# Voltage_Reference.net
KiCad netlist of a schematic drawn in Altium Designer
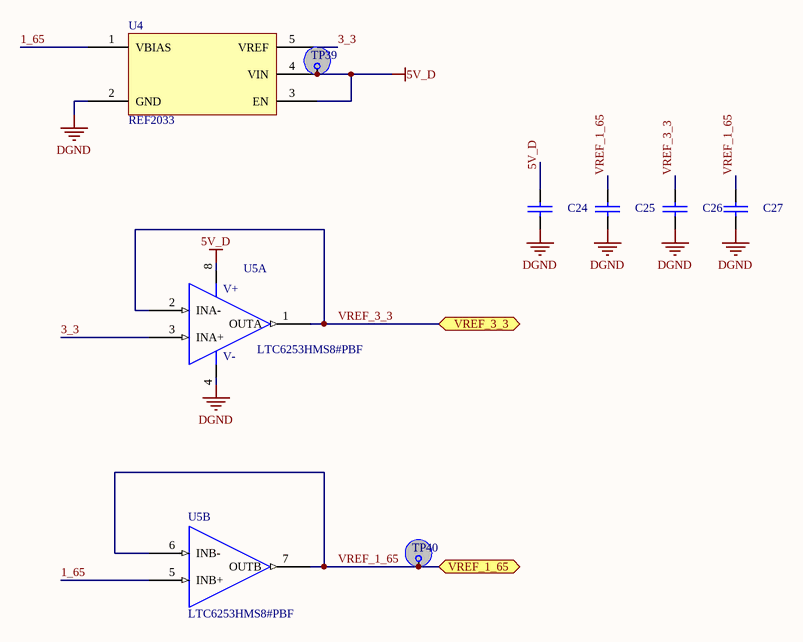
[diagram p0: Voltage Reference.SchDoc]

(export (version "E")
  (design (tool "Eeschema 10.0.6"))
  (components
    (comp (ref "C24")
      (value "CAP 0603 100nF 100V")
      (footprint "CAPC1608N")
      (description "CAP 0603 TBD")
      (fields (field (name "PART#") "TBD"))
      (libsource (lib "SMD_R&C_V1.0") (part "CAP 0603 TBD"))
    )
    (comp (ref "C25")
      (value "CAP 0603 100nF 100V")
      (footprint "CAPC1608N")
      (description "CAP 0603 TBD")
      (fields (field (name "PART#") "TBD"))
      (libsource (lib "SMD_R&C_V1.0") (part "CAP 0603 TBD"))
    )
    (comp (ref "C26")
      (value "CAP 0603 100nF 100V")
      (footprint "CAPC1608N")
      (description "CAP 0603 TBD")
      (fields (field (name "PART#") "TBD"))
      (libsource (lib "SMD_R&C_V1.0") (part "CAP 0603 TBD"))
    )
    (comp (ref "C27")
      (value "CAP 0603 100nF 100V")
      (footprint "CAPC1608N")
      (description "CAP 0603 TBD")
      (fields (field (name "PART#") "TBD"))
      (libsource (lib "SMD_R&C_V1.0") (part "CAP 0603 TBD"))
    )
    (comp (ref "TP39")
      (value "*")
      (footprint "Keystone 5000")
      (libsource (lib "Aarons_Library") (part "TEST_POINT_HOOK"))
    )
    (comp (ref "TP40")
      (value "*")
      (footprint "Keystone 5000")
      (libsource (lib "Aarons_Library") (part "TEST_POINT_HOOK"))
    )
    (comp (ref "U4")
      (value "REF2033")
      (footprint "SOT-23 5 PIN")
      (libsource (lib "Aarons_Library") (part "REF2033"))
    )
    (comp (ref "U5")
      (value "LTC6253HMS8#PBF")
      (footprint "SOIC-8")
      (description "720MHz, 3.5mA Power\r\nEfficient Rail-to-Rail\r\nI/O Op Amps")
      (fields
        (field (name "MANUFACTURER") "Texas Instruments")
        (field (name "GENERIC_PART_NUMBER") "OPA2140")
      )
      (libsource (lib "Analog_Op-amp") (part "LTC6253HMS8#PBF"))
    )
  )
  (nets
    (net (code "1") (name "/1_65") (class "Default")
      (node (ref "U4") (pin "1") (pinfunction "VBIAS_1") (pintype "passive"))
      (node (ref "U5") (pin "5") (pinfunction "INB+_5") (pintype "input"))
    )
    (net (code "2") (name "/3_3") (class "Default")
      (node (ref "U4") (pin "5") (pinfunction "VREF_5") (pintype "passive"))
      (node (ref "U5") (pin "3") (pinfunction "INA+_3") (pintype "input"))
    )
    (net (code "3") (name "/VREF_1_65") (class "Default")
      (node (ref "C25") (pin "2") (pintype "passive"))
      (node (ref "C27") (pin "2") (pintype "passive"))
      (node (ref "TP40") (pin "1") (pinfunction "1_1") (pintype "passive"))
      (node (ref "U5") (pin "6") (pinfunction "INB-_6") (pintype "input"))
      (node (ref "U5") (pin "7") (pinfunction "OUTB_7") (pintype "output"))
    )
    (net (code "4") (name "/VREF_3_3") (class "Default")
      (node (ref "C26") (pin "2") (pintype "passive"))
      (node (ref "U5") (pin "1") (pinfunction "OUTA_1") (pintype "output"))
      (node (ref "U5") (pin "2") (pinfunction "INA-_2") (pintype "input"))
    )
    (net (code "5") (name "5V_D") (class "Default")
      (node (ref "C24") (pin "2") (pintype "passive"))
      (node (ref "TP39") (pin "1") (pinfunction "1_1") (pintype "passive"))
      (node (ref "U4") (pin "3") (pinfunction "EN_3") (pintype "passive"))
      (node (ref "U4") (pin "4") (pinfunction "VIN_4") (pintype "passive"))
      (node (ref "U5") (pin "8") (pinfunction "V+_8") (pintype "power_in"))
    )
    (net (code "6") (name "DGND") (class "Default")
      (node (ref "C24") (pin "1") (pintype "passive"))
      (node (ref "C25") (pin "1") (pintype "passive"))
      (node (ref "C26") (pin "1") (pintype "passive"))
      (node (ref "C27") (pin "1") (pintype "passive"))
      (node (ref "U4") (pin "2") (pinfunction "GND_2") (pintype "passive"))
      (node (ref "U5") (pin "4") (pinfunction "V-_4") (pintype "power_in"))
    )
  )
)
